# mapleCUx_large_056.net
KiCad netlist of a schematic drawn in EAGLE
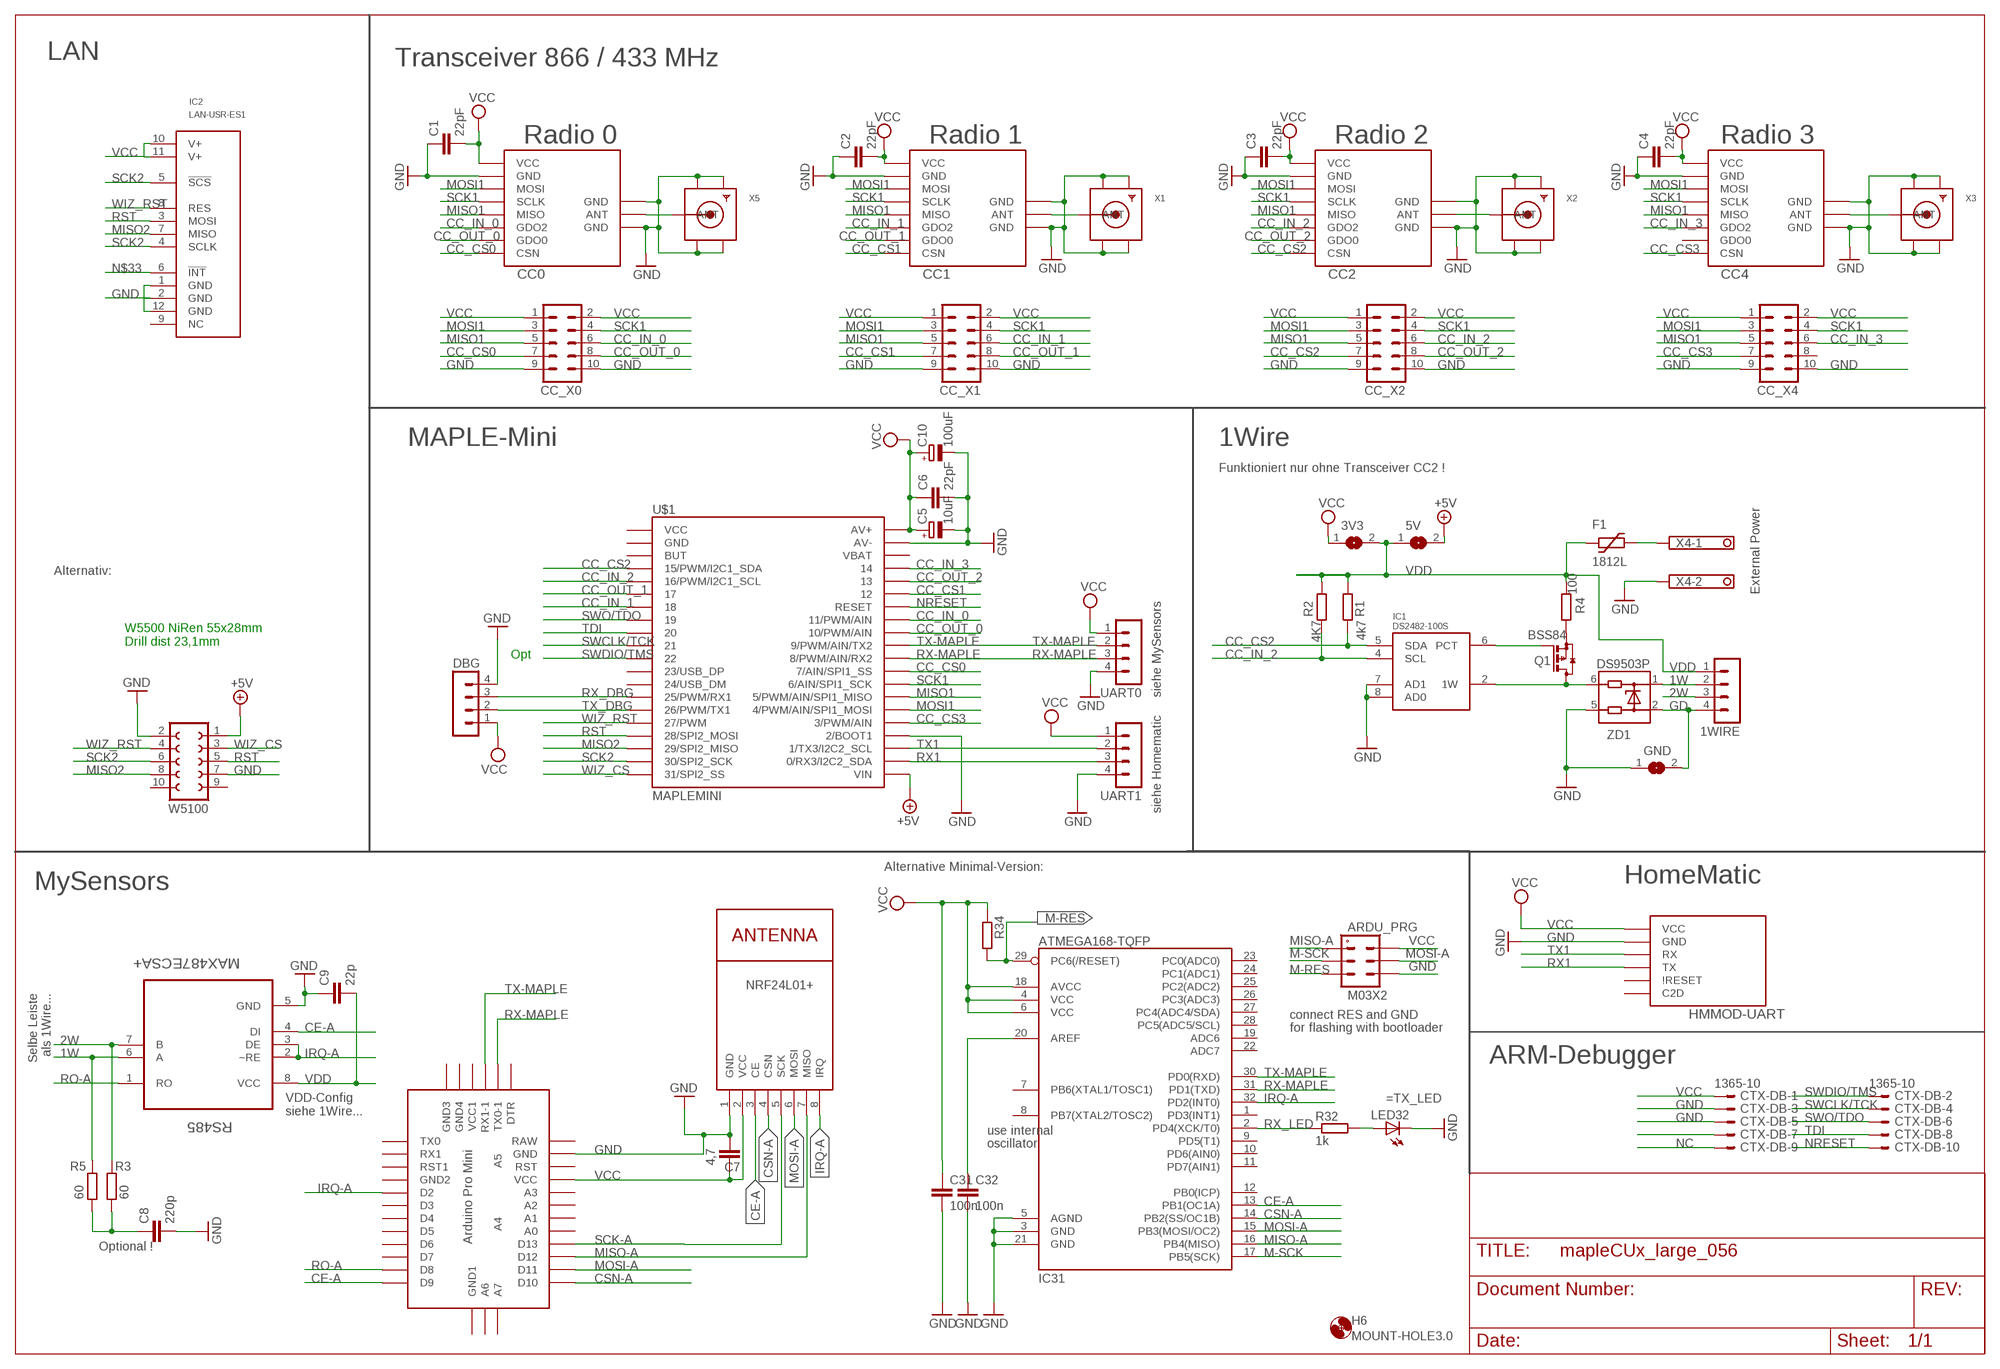
[diagram p0: schematic, sheet 1]

(export (version "E")
  (design (tool "Eeschema 10.0.6"))
  (components
    (comp (ref "1WIRE")
      (value "MA04-1")
      (footprint "eagle-import:MA04-1")
      (libsource (lib "eagle-import") (part "MA04-1"))
    )
    (comp (ref "3V3") (value "SJ") (footprint "eagle-import:SJ") (libsource (lib "eagle-import") (part "SJ")))
    (comp (ref "5V") (value "SJ") (footprint "eagle-import:SJ") (libsource (lib "eagle-import") (part "SJ")))
    (comp (ref "ARDU_PRG")
      (value "M03X2")
      (footprint "eagle-import:2X03-1.27MM_SMD")
      (libsource (lib "eagle-import") (part "M03X2"))
    )
    (comp (ref "C1")
      (value "22pF")
      (footprint "eagle-import:C0805")
      (libsource (lib "eagle-import") (part "C-EUC0805"))
    )
    (comp (ref "C2")
      (value "22pF")
      (footprint "eagle-import:C0805")
      (libsource (lib "eagle-import") (part "C-EUC0805"))
    )
    (comp (ref "C3")
      (value "22pF")
      (footprint "eagle-import:C0805")
      (libsource (lib "eagle-import") (part "C-EUC0805"))
    )
    (comp (ref "C4")
      (value "22pF")
      (footprint "eagle-import:C0805")
      (libsource (lib "eagle-import") (part "C-EUC0805"))
    )
    (comp (ref "C5")
      (value "10uF")
      (footprint "eagle-import:R_2012-12W")
      (libsource (lib "eagle-import") (part "CPOL-EUR/2012-12W"))
    )
    (comp (ref "C6")
      (value "22pF")
      (footprint "eagle-import:C0805")
      (libsource (lib "eagle-import") (part "C-EUC0805"))
    )
    (comp (ref "C7")
      (value "4,7")
      (footprint "eagle-import:C1210")
      (libsource (lib "eagle-import") (part "C-EUC1210"))
    )
    (comp (ref "C8")
      (value "220p")
      (footprint "eagle-import:C0805")
      (libsource (lib "eagle-import") (part "C-EUC0805"))
    )
    (comp (ref "C9")
      (value "22p")
      (footprint "eagle-import:C0805")
      (libsource (lib "eagle-import") (part "C-EUC0805"))
    )
    (comp (ref "C10")
      (value "100uF")
      (footprint "eagle-import:E5-8,5")
      (libsource (lib "eagle-import") (part "CPOL-EUE5-8.5"))
    )
    (comp (ref "C31")
      (value "100n")
      (footprint "eagle-import:C0805")
      (libsource (lib "eagle-import") (part "C-EUC0805"))
    )
    (comp (ref "C32")
      (value "100n")
      (footprint "eagle-import:C0805")
      (libsource (lib "eagle-import") (part "C-EUC0805"))
    )
    (comp (ref "CC0")
      (value "CC1101_MODULE1SMD")
      (footprint "eagle-import:CC1101_MODULE1_SMD")
      (libsource (lib "eagle-import") (part "CC1101_MODULE1SMD"))
    )
    (comp (ref "CC1")
      (value "CC1101_MODULE1SMD")
      (footprint "eagle-import:CC1101_MODULE1_SMD")
      (libsource (lib "eagle-import") (part "CC1101_MODULE1SMD"))
    )
    (comp (ref "CC2")
      (value "CC1101_MODULE1SMD")
      (footprint "eagle-import:CC1101_MODULE1_SMD")
      (libsource (lib "eagle-import") (part "CC1101_MODULE1SMD"))
    )
    (comp (ref "CC4")
      (value "CC1101_MODULE1SMD")
      (footprint "eagle-import:CC1101_MODULE1_SMD")
      (libsource (lib "eagle-import") (part "CC1101_MODULE1SMD"))
    )
    (comp (ref "CC_X0")
      (value "MA05-2")
      (footprint "eagle-import:MA05-2")
      (libsource (lib "eagle-import") (part "MA05-2"))
    )
    (comp (ref "CC_X1")
      (value "MA05-2")
      (footprint "eagle-import:MA05-2")
      (libsource (lib "eagle-import") (part "MA05-2"))
    )
    (comp (ref "CC_X2")
      (value "MA05-2")
      (footprint "eagle-import:MA05-2")
      (libsource (lib "eagle-import") (part "MA05-2"))
    )
    (comp (ref "CC_X4")
      (value "MA05-2")
      (footprint "eagle-import:MA05-2")
      (libsource (lib "eagle-import") (part "MA05-2"))
    )
    (comp (ref "CTX-DB")
      (value "1365-10")
      (footprint "eagle-import:1365-10")
      (libsource (lib "eagle-import") (part "1365-10"))
    )
    (comp (ref "DBG")
      (value "MA04-1")
      (footprint "eagle-import:MA04-1")
      (libsource (lib "eagle-import") (part "MA04-1"))
    )
    (comp (ref "F1")
      (value "1812L")
      (footprint "eagle-import:1812L")
      (libsource (lib "eagle-import") (part "1812L"))
    )
    (comp (ref "GND") (value "SJ") (footprint "eagle-import:SJ") (libsource (lib "eagle-import") (part "SJ")))
    (comp (ref "H6")
      (value "MOUNT-HOLE3.0")
      (footprint "eagle-import:3,0")
      (libsource (lib "eagle-import") (part "MOUNT-HOLE3.0"))
    )
    (comp (ref "HMMOD-UART")
      (value "HM-MOD-UARTDIL")
      (footprint "eagle-import:HM-MOD-UART-DIL")
      (libsource (lib "eagle-import") (part "HM-MOD-UARTDIL"))
    )
    (comp (ref "IC1")
      (value "DS2482-100S")
      (footprint "eagle-import:SO08")
      (libsource (lib "eagle-import") (part "DS2482-100S"))
    )
    (comp (ref "IC2")
      (value "LAN-USR-ES1")
      (footprint "eagle-import:USR-ES1")
      (libsource (lib "eagle-import") (part "LAN-USR-ES1"))
    )
    (comp (ref "IC31")
      (value "ATMEGA168-TQFP")
      (footprint "eagle-import:TQFP32-08")
      (libsource (lib "eagle-import") (part "ATMEGA168-TQFP"))
    )
    (comp (ref "LED32")
      (value "LEDCHIPLED_0805")
      (footprint "eagle-import:CHIPLED_0805")
      (libsource (lib "eagle-import") (part "LEDCHIPLED_0805"))
    )
    (comp (ref "NRF24L01+")
      (value "NRF24L01+")
      (footprint "eagle-import:WIRELESS-NRF24L01")
      (libsource (lib "eagle-import") (part "WIRELESS-NRF24L01"))
    )
    (comp (ref "Q1")
      (value "BSS84")
      (footprint "eagle-import:SOT23")
      (libsource (lib "eagle-import") (part "BSS84"))
    )
    (comp (ref "R1")
      (value "4k7")
      (footprint "eagle-import:R0805")
      (libsource (lib "eagle-import") (part "R-EU_R0805"))
    )
    (comp (ref "R2")
      (value "4K7")
      (footprint "eagle-import:R0805")
      (libsource (lib "eagle-import") (part "R-EU_R0805"))
    )
    (comp (ref "R3")
      (value "60")
      (footprint "eagle-import:R0805")
      (libsource (lib "eagle-import") (part "R-EU_R0805"))
    )
    (comp (ref "R4")
      (value "100")
      (footprint "eagle-import:R0805")
      (libsource (lib "eagle-import") (part "R-EU_R0805"))
    )
    (comp (ref "R5")
      (value "60")
      (footprint "eagle-import:R0805")
      (libsource (lib "eagle-import") (part "R-EU_R0805"))
    )
    (comp (ref "R32")
      (value "1k")
      (footprint "eagle-import:R0805")
      (libsource (lib "eagle-import") (part "R-EU_R0805"))
    )
    (comp (ref "R34")
      (value "R-EU_R0805")
      (footprint "eagle-import:R0805")
      (libsource (lib "eagle-import") (part "R-EU_R0805"))
    )
    (comp (ref "RS485")
      (value "MAX487ECSA+")
      (footprint "eagle-import:SOIC127P600X175-8N")
      (libsource (lib "eagle-import") (part "MAX487ECSA+"))
    )
    (comp (ref "U$1")
      (value "MAPLEMINI")
      (footprint "eagle-import:20-DIP")
      (libsource (lib "eagle-import") (part "MAPLEMINI"))
    )
    (comp (ref "U$2")
      (value "ABK-PRO-MINI")
      (footprint "eagle-import:ABK-PRO-MINI")
      (libsource (lib "eagle-import") (part "ABK-PRO-MINI"))
    )
    (comp (ref "UART0")
      (value "MA04-1")
      (footprint "eagle-import:MA04-1")
      (libsource (lib "eagle-import") (part "MA04-1"))
    )
    (comp (ref "UART1")
      (value "MA04-1")
      (footprint "eagle-import:MA04-1")
      (libsource (lib "eagle-import") (part "MA04-1"))
    )
    (comp (ref "W5100")
      (value "FE05-2")
      (footprint "eagle-import:FE05-2")
      (libsource (lib "eagle-import") (part "FE05-2"))
    )
    (comp (ref "X1")
      (value "SMACONNECTOR_EDGE_UFL")
      (footprint "eagle-import:SMA_EDGELAUNCH_UFL")
      (libsource (lib "eagle-import") (part "SMACONNECTOR_EDGE_UFL"))
    )
    (comp (ref "X2")
      (value "SMACONNECTOR_EDGE_UFL")
      (footprint "eagle-import:SMA_EDGELAUNCH_UFL")
      (libsource (lib "eagle-import") (part "SMACONNECTOR_EDGE_UFL"))
    )
    (comp (ref "X3")
      (value "SMACONNECTOR_EDGE_UFL")
      (footprint "eagle-import:SMA_EDGELAUNCH_UFL")
      (libsource (lib "eagle-import") (part "SMACONNECTOR_EDGE_UFL"))
    )
    (comp (ref "X4")
      (value "1751248")
      (footprint "eagle-import:1751248")
      (libsource (lib "eagle-import") (part "1751248"))
    )
    (comp (ref "X5")
      (value "SMACONNECTOR_EDGE_UFL")
      (footprint "eagle-import:SMA_EDGELAUNCH_UFL")
      (libsource (lib "eagle-import") (part "SMACONNECTOR_EDGE_UFL"))
    )
    (comp (ref "ZD1")
      (value "DS9503P")
      (footprint "eagle-import:TSOC6")
      (libsource (lib "eagle-import") (part "DS9503P"))
    )
  )
  (nets
    (net (code "1") (name "+5V") (class "Default")
      (node (ref "5V") (pin "2") (pinfunction "2_2") (pintype "passive"))
      (node (ref "U$1") (pin "21") (pinfunction "VIN_21") (pintype "bidirectional"))
      (node (ref "W5100") (pin "1") (pinfunction "1_1") (pintype "passive"))
    )
    (net (code "2") (name "/1W") (class "Default")
      (node (ref "1WIRE") (pin "2") (pinfunction "2_2") (pintype "passive"))
      (node (ref "R5") (pin "2") (pinfunction "2_2") (pintype "passive"))
      (node (ref "RS485") (pin "6") (pinfunction "A_6") (pintype "bidirectional"))
      (node (ref "ZD1") (pin "1") (pinfunction "P$1_1") (pintype "passive"))
    )
    (net (code "3") (name "/2W") (class "Default")
      (node (ref "1WIRE") (pin "3") (pinfunction "3_3") (pintype "passive"))
      (node (ref "R3") (pin "2") (pinfunction "2_2") (pintype "passive"))
      (node (ref "RS485") (pin "7") (pinfunction "B_7") (pintype "bidirectional"))
    )
    (net (code "4") (name "/CC_CS0") (class "Default")
      (node (ref "CC0") (pin "CSN") (pinfunction "CSN_CSN") (pintype "bidirectional"))
      (node (ref "CC_X0") (pin "7") (pinfunction "7_7") (pintype "passive"))
      (node (ref "U$1") (pin "29") (pinfunction "7/AIN/SPI1_SS_29") (pintype "bidirectional"))
    )
    (net (code "5") (name "/CC_CS1") (class "Default")
      (node (ref "CC1") (pin "CSN") (pinfunction "CSN_CSN") (pintype "bidirectional"))
      (node (ref "CC_X1") (pin "7") (pinfunction "7_7") (pintype "passive"))
      (node (ref "U$1") (pin "35") (pinfunction "12_35") (pintype "bidirectional"))
    )
    (net (code "6") (name "/CC_CS2") (class "Default")
      (node (ref "CC2") (pin "CSN") (pinfunction "CSN_CSN") (pintype "bidirectional"))
      (node (ref "CC_X2") (pin "7") (pinfunction "7_7") (pintype "passive"))
      (node (ref "IC1") (pin "5") (pinfunction "SDA_5") (pintype "bidirectional"))
      (node (ref "R1") (pin "2") (pinfunction "2_2") (pintype "passive"))
      (node (ref "U$1") (pin "4") (pinfunction "15/PWM/I2C1_SDA_4") (pintype "bidirectional"))
    )
    (net (code "7") (name "/CC_CS3") (class "Default")
      (node (ref "CC4") (pin "CSN") (pinfunction "CSN_CSN") (pintype "bidirectional"))
      (node (ref "CC_X4") (pin "7") (pinfunction "7_7") (pintype "passive"))
      (node (ref "U$1") (pin "25") (pinfunction "3/PWM/AIN_25") (pintype "bidirectional"))
    )
    (net (code "8") (name "/CC_IN_0") (class "Default")
      (node (ref "CC0") (pin "GDO2") (pinfunction "GDO2_GDO2") (pintype "bidirectional"))
      (node (ref "CC_X0") (pin "6") (pinfunction "6_6") (pintype "passive"))
      (node (ref "U$1") (pin "33") (pinfunction "11/PWM/AIN_33") (pintype "bidirectional"))
    )
    (net (code "9") (name "/CC_IN_1") (class "Default")
      (node (ref "CC1") (pin "GDO2") (pinfunction "GDO2_GDO2") (pintype "bidirectional"))
      (node (ref "CC_X1") (pin "6") (pinfunction "6_6") (pintype "passive"))
      (node (ref "U$1") (pin "7") (pinfunction "18_7") (pintype "bidirectional"))
    )
    (net (code "10") (name "/CC_IN_2") (class "Default")
      (node (ref "CC2") (pin "GDO2") (pinfunction "GDO2_GDO2") (pintype "bidirectional"))
      (node (ref "CC_X2") (pin "6") (pinfunction "6_6") (pintype "passive"))
      (node (ref "IC1") (pin "4") (pinfunction "SCL_4") (pintype "input"))
      (node (ref "R2") (pin "2") (pinfunction "2_2") (pintype "passive"))
      (node (ref "U$1") (pin "5") (pinfunction "16/PWM/I2C1_SCL_5") (pintype "bidirectional"))
    )
    (net (code "11") (name "/CC_IN_3") (class "Default")
      (node (ref "CC4") (pin "GDO2") (pinfunction "GDO2_GDO2") (pintype "bidirectional"))
      (node (ref "CC_X4") (pin "6") (pinfunction "6_6") (pintype "passive"))
      (node (ref "U$1") (pin "37") (pinfunction "14_37") (pintype "bidirectional"))
    )
    (net (code "12") (name "/CC_OUT_0") (class "Default")
      (node (ref "CC0") (pin "GDO0") (pinfunction "GDO0_GDO0") (pintype "bidirectional"))
      (node (ref "CC_X0") (pin "8") (pinfunction "8_8") (pintype "passive"))
      (node (ref "U$1") (pin "32") (pinfunction "10/PWM/AIN_32") (pintype "bidirectional"))
    )
    (net (code "13") (name "/CC_OUT_1") (class "Default")
      (node (ref "CC1") (pin "GDO0") (pinfunction "GDO0_GDO0") (pintype "bidirectional"))
      (node (ref "CC_X1") (pin "8") (pinfunction "8_8") (pintype "passive"))
      (node (ref "U$1") (pin "6") (pinfunction "17_6") (pintype "bidirectional"))
    )
    (net (code "14") (name "/CC_OUT_2") (class "Default")
      (node (ref "CC2") (pin "GDO0") (pinfunction "GDO0_GDO0") (pintype "bidirectional"))
      (node (ref "CC_X2") (pin "8") (pinfunction "8_8") (pintype "passive"))
      (node (ref "U$1") (pin "36") (pinfunction "13_36") (pintype "bidirectional"))
    )
    (net (code "15") (name "/GD") (class "Default")
      (node (ref "1WIRE") (pin "4") (pinfunction "4_4") (pintype "passive"))
      (node (ref "GND") (pin "2") (pinfunction "2_2") (pintype "passive"))
      (node (ref "ZD1") (pin "2") (pinfunction "P$2_2") (pintype "passive"))
    )
    (net (code "16") (name "/M-RES") (class "Default")
      (node (ref "ARDU_PRG") (pin "P$5") (pinfunction "5_P$5") (pintype "passive"))
      (node (ref "IC31") (pin "29") (pinfunction "PC6(/RESET)_29") (pintype "bidirectional"))
      (node (ref "R34") (pin "2") (pinfunction "2_2") (pintype "passive"))
    )
    (net (code "17") (name "/M-SCK") (class "Default")
      (node (ref "ARDU_PRG") (pin "P$3") (pinfunction "3_P$3") (pintype "passive"))
      (node (ref "IC31") (pin "17") (pinfunction "PB5(SCK)_17") (pintype "bidirectional"))
    )
    (net (code "18") (name "/MISO-A") (class "Default")
      (node (ref "ARDU_PRG") (pin "P$1") (pinfunction "1_P$1") (pintype "passive"))
      (node (ref "IC31") (pin "16") (pinfunction "PB4(MISO)_16") (pintype "bidirectional"))
      (node (ref "NRF24L01+") (pin "7") (pinfunction "MISO_7") (pintype "bidirectional"))
      (node (ref "U$2") (pin "D12") (pinfunction "D12_D12") (pintype "bidirectional"))
    )
    (net (code "19") (name "/MISO1") (class "Default")
      (node (ref "CC0") (pin "MISO") (pinfunction "MISO_MISO") (pintype "bidirectional"))
      (node (ref "CC1") (pin "MISO") (pinfunction "MISO_MISO") (pintype "bidirectional"))
      (node (ref "CC2") (pin "MISO") (pinfunction "MISO_MISO") (pintype "bidirectional"))
      (node (ref "CC4") (pin "MISO") (pinfunction "MISO_MISO") (pintype "bidirectional"))
      (node (ref "CC_X0") (pin "5") (pinfunction "5_5") (pintype "passive"))
      (node (ref "CC_X1") (pin "5") (pinfunction "5_5") (pintype "passive"))
      (node (ref "CC_X2") (pin "5") (pinfunction "5_5") (pintype "passive"))
      (node (ref "CC_X4") (pin "5") (pinfunction "5_5") (pintype "passive"))
      (node (ref "U$1") (pin "27") (pinfunction "5/PWM/AIN/SPI1_MISO_27") (pintype "bidirectional"))
    )
    (net (code "20") (name "/MISO2") (class "Default")
      (node (ref "IC2") (pin "7") (pinfunction "MISO_7") (pintype "bidirectional"))
      (node (ref "U$1") (pin "18") (pinfunction "29/SPI2_MISO_18") (pintype "bidirectional"))
      (node (ref "W5100") (pin "8") (pinfunction "8_8") (pintype "passive"))
    )
    (net (code "21") (name "/MOSI1") (class "Default")
      (node (ref "CC0") (pin "MOSI") (pinfunction "MOSI_MOSI") (pintype "bidirectional"))
      (node (ref "CC1") (pin "MOSI") (pinfunction "MOSI_MOSI") (pintype "bidirectional"))
      (node (ref "CC2") (pin "MOSI") (pinfunction "MOSI_MOSI") (pintype "bidirectional"))
      (node (ref "CC4") (pin "MOSI") (pinfunction "MOSI_MOSI") (pintype "bidirectional"))
      (node (ref "CC_X0") (pin "3") (pinfunction "3_3") (pintype "passive"))
      (node (ref "CC_X1") (pin "3") (pinfunction "3_3") (pintype "passive"))
      (node (ref "CC_X2") (pin "3") (pinfunction "3_3") (pintype "passive"))
      (node (ref "CC_X4") (pin "3") (pinfunction "3_3") (pintype "passive"))
      (node (ref "U$1") (pin "26") (pinfunction "4/PWM/AIN/SPI1_MOSI_26") (pintype "bidirectional"))
    )
    (net (code "22") (name "/N$33") (class "Default")
      (node (ref "IC2") (pin "6") (pinfunction "~{INT}_6") (pintype "output"))
    )
    (net (code "23") (name "/NC") (class "Default")
      (node (ref "CTX-DB") (pin "9") (pinfunction "S_9") (pintype "passive"))
    )
    (net (code "24") (name "/NRESET") (class "Default")
      (node (ref "CTX-DB") (pin "10") (pinfunction "S_10") (pintype "passive"))
      (node (ref "U$1") (pin "34") (pinfunction "RESET_34") (pintype "bidirectional"))
    )
    (net (code "25") (name "/RO-A") (class "Default")
      (node (ref "RS485") (pin "1") (pinfunction "RO_1") (pintype "output"))
      (node (ref "U$2") (pin "D8") (pinfunction "D8_D8") (pintype "bidirectional"))
    )
    (net (code "26") (name "/RST") (class "Default")
      (node (ref "IC2") (pin "3") (pinfunction "MOSI_3") (pintype "bidirectional"))
      (node (ref "U$1") (pin "17") (pinfunction "28/SPI2_MOSI_17") (pintype "bidirectional"))
      (node (ref "W5100") (pin "5") (pinfunction "5_5") (pintype "passive"))
    )
    (net (code "27") (name "/RX-MAPLE") (class "Default")
      (node (ref "IC31") (pin "31") (pinfunction "PD1(TXD)_31") (pintype "bidirectional"))
      (node (ref "U$1") (pin "30") (pinfunction "8/PWM/AIN/RX2_30") (pintype "bidirectional"))
      (node (ref "U$2") (pin "TX0-1") (pinfunction "TX0-1_TX0-1") (pintype "bidirectional"))
      (node (ref "UART0") (pin "3") (pinfunction "3_3") (pintype "passive"))
    )
    (net (code "28") (name "/RX1") (class "Default")
      (node (ref "HMMOD-UART") (pin "5") (pinfunction "TX_5") (pintype "bidirectional"))
      (node (ref "U$1") (pin "22") (pinfunction "0/RX3/I2C2_SDA_22") (pintype "bidirectional"))
      (node (ref "UART1") (pin "3") (pinfunction "3_3") (pintype "passive"))
    )
    (net (code "29") (name "/RX_DBG") (class "Default")
      (node (ref "DBG") (pin "3") (pinfunction "3_3") (pintype "passive"))
      (node (ref "U$1") (pin "14") (pinfunction "25/PWM/RX1_14") (pintype "bidirectional"))
    )
    (net (code "30") (name "/RX_LED") (class "Default")
      (node (ref "IC31") (pin "2") (pinfunction "PD4(XCK/T0)_2") (pintype "bidirectional"))
      (node (ref "R32") (pin "1") (pinfunction "1_1") (pintype "passive"))
    )
    (net (code "31") (name "/SCK-A") (class "Default")
      (node (ref "NRF24L01+") (pin "5") (pinfunction "SCK_5") (pintype "bidirectional"))
      (node (ref "U$2") (pin "D13") (pinfunction "D13_D13") (pintype "bidirectional"))
    )
    (net (code "32") (name "/SCK1") (class "Default")
      (node (ref "CC0") (pin "SCLK") (pinfunction "SCLK_SCLK") (pintype "bidirectional"))
      (node (ref "CC1") (pin "SCLK") (pinfunction "SCLK_SCLK") (pintype "bidirectional"))
      (node (ref "CC2") (pin "SCLK") (pinfunction "SCLK_SCLK") (pintype "bidirectional"))
      (node (ref "CC4") (pin "SCLK") (pinfunction "SCLK_SCLK") (pintype "bidirectional"))
      (node (ref "CC_X0") (pin "4") (pinfunction "4_4") (pintype "passive"))
      (node (ref "CC_X1") (pin "4") (pinfunction "4_4") (pintype "passive"))
      (node (ref "CC_X2") (pin "4") (pinfunction "4_4") (pintype "passive"))
      (node (ref "CC_X4") (pin "4") (pinfunction "4_4") (pintype "passive"))
      (node (ref "U$1") (pin "28") (pinfunction "6/AIN/SPI1_SCK_28") (pintype "bidirectional"))
    )
    (net (code "33") (name "/SCK2") (class "Default")
      (node (ref "IC2") (pin "4") (pinfunction "SCLK_4") (pintype "input"))
      (node (ref "IC2") (pin "5") (pinfunction "~{SCS}_5") (pintype "input"))
      (node (ref "U$1") (pin "19") (pinfunction "30/SPI2_SCK_19") (pintype "bidirectional"))
      (node (ref "W5100") (pin "6") (pinfunction "6_6") (pintype "passive"))
    )
    (net (code "34") (name "/SWCLK{slash}TCK") (class "Default")
      (node (ref "CTX-DB") (pin "4") (pinfunction "S_4") (pintype "passive"))
      (node (ref "U$1") (pin "10") (pinfunction "21_10") (pintype "bidirectional"))
    )
    (net (code "35") (name "/SWDIO{slash}TMS") (class "Default")
      (node (ref "CTX-DB") (pin "2") (pinfunction "S_2") (pintype "passive"))
      (node (ref "U$1") (pin "11") (pinfunction "22_11") (pintype "bidirectional"))
    )
    (net (code "36") (name "/SWO{slash}TDO") (class "Default")
      (node (ref "CTX-DB") (pin "6") (pinfunction "S_6") (pintype "passive"))
      (node (ref "U$1") (pin "8") (pinfunction "19_8") (pintype "bidirectional"))
    )
    (net (code "37") (name "/TDI") (class "Default")
      (node (ref "CTX-DB") (pin "8") (pinfunction "S_8") (pintype "passive"))
      (node (ref "U$1") (pin "9") (pinfunction "20_9") (pintype "bidirectional"))
    )
    (net (code "38") (name "/TX-MAPLE") (class "Default")
      (node (ref "IC31") (pin "30") (pinfunction "PD0(RXD)_30") (pintype "bidirectional"))
      (node (ref "U$1") (pin "31") (pinfunction "9/PWM/AIN/TX2_31") (pintype "bidirectional"))
      (node (ref "U$2") (pin "RX1-1") (pinfunction "RX1-1_RX1-1") (pintype "bidirectional"))
      (node (ref "UART0") (pin "2") (pinfunction "2_2") (pintype "passive"))
    )
    (net (code "39") (name "/TX1") (class "Default")
      (node (ref "HMMOD-UART") (pin "6") (pinfunction "RX_6") (pintype "bidirectional"))
      (node (ref "U$1") (pin "23") (pinfunction "1/TX3/I2C2_SCL_23") (pintype "bidirectional"))
      (node (ref "UART1") (pin "2") (pinfunction "2_2") (pintype "passive"))
    )
    (net (code "40") (name "/TX_DBG") (class "Default")
      (node (ref "DBG") (pin "2") (pinfunction "2_2") (pintype "passive"))
      (node (ref "U$1") (pin "15") (pinfunction "26/PWM/TX1_15") (pintype "bidirectional"))
    )
    (net (code "41") (name "/VDD") (class "Default")
      (node (ref "1WIRE") (pin "1") (pinfunction "1_1") (pintype "passive"))
      (node (ref "3V3") (pin "2") (pinfunction "2_2") (pintype "passive"))
      (node (ref "5V") (pin "1") (pinfunction "1_1") (pintype "passive"))
      (node (ref "C9") (pin "2") (pinfunction "2_2") (pintype "passive"))
      (node (ref "F1") (pin "P$1") (pinfunction "1_P$1") (pintype "passive"))
      (node (ref "R1") (pin "1") (pinfunction "1_1") (pintype "passive"))
      (node (ref "R2") (pin "1") (pinfunction "1_1") (pintype "passive"))
      (node (ref "R4") (pin "2") (pinfunction "2_2") (pintype "passive"))
      (node (ref "RS485") (pin "8") (pinfunction "VCC_8") (pintype "power_in"))
    )
    (net (code "42") (name "/WIZ_CS") (class "Default")
      (node (ref "U$1") (pin "20") (pinfunction "31/SPI2_SS_20") (pintype "bidirectional"))
      (node (ref "W5100") (pin "3") (pinfunction "3_3") (pintype "passive"))
    )
    (net (code "43") (name "/WIZ_RST") (class "Default")
      (node (ref "IC2") (pin "8") (pinfunction "RES_8") (pintype "input"))
      (node (ref "U$1") (pin "16") (pinfunction "27/PWM_16") (pintype "bidirectional"))
      (node (ref "W5100") (pin "4") (pinfunction "4_4") (pintype "passive"))
    )
    (net (code "44") (name "CE-A") (class "Default")
      (node (ref "IC31") (pin "13") (pinfunction "PB1(OC1A)_13") (pintype "bidirectional"))
      (node (ref "NRF24L01+") (pin "3") (pinfunction "CE_3") (pintype "bidirectional"))
      (node (ref "RS485") (pin "4") (pinfunction "DI_4") (pintype "input"))
      (node (ref "U$2") (pin "D9") (pinfunction "D9_D9") (pintype "bidirectional"))
    )
    (net (code "45") (name "CSN-A") (class "Default")
      (node (ref "IC31") (pin "14") (pinfunction "PB2(SS/OC1B)_14") (pintype "bidirectional"))
      (node (ref "NRF24L01+") (pin "4") (pinfunction "CSN_4") (pintype "bidirectional"))
      (node (ref "U$2") (pin "D10") (pinfunction "D10_D10") (pintype "bidirectional"))
    )
    (net (code "46") (name "GND") (class "Default")
      (node (ref "ARDU_PRG") (pin "P$6") (pinfunction "6_P$6") (pintype "passive"))
      (node (ref "C1") (pin "1") (pinfunction "1_1") (pintype "passive"))
      (node (ref "C10") (pin "-") (pinfunction "-_-") (pintype "passive"))
      (node (ref "C2") (pin "1") (pinfunction "1_1") (pintype "passive"))
      (node (ref "C3") (pin "1") (pinfunction "1_1") (pintype "passive"))
      (node (ref "C31") (pin "2") (pinfunction "2_2") (pintype "passive"))
      (node (ref "C32") (pin "2") (pinfunction "2_2") (pintype "passive"))
      (node (ref "C4") (pin "1") (pinfunction "1_1") (pintype "passive"))
      (node (ref "C5") (pin "-") (pinfunction "-_-") (pintype "passive"))
      (node (ref "C6") (pin "2") (pinfunction "2_2") (pintype "passive"))
      (node (ref "C7") (pin "1") (pinfunction "1_1") (pintype "passive"))
      (node (ref "C8") (pin "2") (pinfunction "2_2") (pintype "passive"))
      (node (ref "C9") (pin "1") (pinfunction "1_1") (pintype "passive"))
      (node (ref "CC0") (pin "GND@0") (pinfunction "GND_GND@0") (pintype "power_in"))
      (node (ref "CC0") (pin "GND@1") (pinfunction "GND_GND@1") (pintype "power_in"))
      (node (ref "CC0") (pin "GND@2") (pinfunction "GND_GND@2") (pintype "power_in"))
      (node (ref "CC1") (pin "GND@0") (pinfunction "GND_GND@0") (pintype "power_in"))
      (node (ref "CC1") (pin "GND@1") (pinfunction "GND_GND@1") (pintype "power_in"))
      (node (ref "CC1") (pin "GND@2") (pinfunction "GND_GND@2") (pintype "power_in"))
      (node (ref "CC2") (pin "GND@0") (pinfunction "GND_GND@0") (pintype "power_in"))
      (node (ref "CC2") (pin "GND@1") (pinfunction "GND_GND@1") (pintype "power_in"))
      (node (ref "CC2") (pin "GND@2") (pinfunction "GND_GND@2") (pintype "power_in"))
      (node (ref "CC4") (pin "GND@0") (pinfunction "GND_GND@0") (pintype "power_in"))
      (node (ref "CC4") (pin "GND@1") (pinfunction "GND_GND@1") (pintype "power_in"))
      (node (ref "CC4") (pin "GND@2") (pinfunction "GND_GND@2") (pintype "power_in"))
      (node (ref "CC_X0") (pin "10") (pinfunction "10_10") (pintype "passive"))
      (node (ref "CC_X0") (pin "9") (pinfunction "9_9") (pintype "passive"))
      (node (ref "CC_X1") (pin "10") (pinfunction "10_10") (pintype "passive"))
      (node (ref "CC_X1") (pin "9") (pinfunction "9_9") (pintype "passive"))
      (node (ref "CC_X2") (pin "10") (pinfunction "10_10") (pintype "passive"))
      (node (ref "CC_X2") (pin "9") (pinfunction "9_9") (pintype "passive"))
      (node (ref "CC_X4") (pin "10") (pinfunction "10_10") (pintype "passive"))
      (node (ref "CC_X4") (pin "9") (pinfunction "9_9") (pintype "passive"))
      (node (ref "CTX-DB") (pin "3") (pinfunction "S_3") (pintype "passive"))
      (node (ref "CTX-DB") (pin "5") (pinfunction "S_5") (pintype "passive"))
      (node (ref "DBG") (pin "4") (pinfunction "4_4") (pintype "passive"))
      (node (ref "GND") (pin "1") (pinfunction "1_1") (pintype "passive"))
      (node (ref "HMMOD-UART") (pin "2") (pinfunction "GND_2") (pintype "power_in"))
      (node (ref "IC1") (pin "7") (pinfunction "AD1_7") (pintype "input"))
      (node (ref "IC1") (pin "8") (pinfunction "AD0_8") (pintype "input"))
      (node (ref "IC2") (pin "1") (pinfunction "GND_1") (pintype "power_in"))
      (node (ref "IC2") (pin "12") (pinfunction "GND_12") (pintype "power_in"))
      (node (ref "IC2") (pin "2") (pinfunction "GND_2") (pintype "power_in"))
      (node (ref "IC31") (pin "21") (pinfunction "GND_21") (pintype "bidirectional"))
      (node (ref "IC31") (pin "3") (pinfunction "GND_3") (pintype "bidirectional"))
      (node (ref "IC31") (pin "5") (pinfunction "AGND_5") (pintype "bidirectional"))
      (node (ref "LED32") (pin "C") (pinfunction "C_C") (pintype "passive"))
      (node (ref "NRF24L01+") (pin "1") (pinfunction "GND_1") (pintype "power_in"))
      (node (ref "RS485") (pin "5") (pinfunction "GND_5") (pintype "passive"))
      (node (ref "U$1") (pin "24") (pinfunction "2/BOOT1_24") (pintype "bidirectional"))
      (node (ref "U$1") (pin "39") (pinfunction "AV-_39") (pintype "bidirectional"))
      (node (ref "U$2") (pin "GND") (pinfunction "GND_GND") (pintype "bidirectional"))
      (node (ref "UART0") (pin "4") (pinfunction "4_4") (pintype "passive"))
      (node (ref "UART1") (pin "4") (pinfunction "4_4") (pintype "passive"))
      (node (ref "W5100") (pin "2") (pinfunction "2_2") (pintype "passive"))
      (node (ref "W5100") (pin "7") (pinfunction "7_7") (pintype "passive"))
      (node (ref "X1") (pin "GND@1") (pinfunction "GND1_GND@1") (pintype "power_in"))
      (node (ref "X1") (pin "GND@2") (pinfunction "GND2_GND@2") (pintype "power_in"))
      (node (ref "X1") (pin "GND@3") (pinfunction "GND3_GND@3") (pintype "power_in"))
      (node (ref "X1") (pin "GND@4") (pinfunction "GND4_GND@4") (pintype "power_in"))
      (node (ref "X2") (pin "GND@1") (pinfunction "GND1_GND@1") (pintype "power_in"))
      (node (ref "X2") (pin "GND@2") (pinfunction "GND2_GND@2") (pintype "power_in"))
      (node (ref "X2") (pin "GND@3") (pinfunction "GND3_GND@3") (pintype "power_in"))
      (node (ref "X2") (pin "GND@4") (pinfunction "GND4_GND@4") (pintype "power_in"))
      (node (ref "X3") (pin "GND@1") (pinfunction "GND1_GND@1") (pintype "power_in"))
      (node (ref "X3") (pin "GND@2") (pinfunction "GND2_GND@2") (pintype "power_in"))
      (node (ref "X3") (pin "GND@3") (pinfunction "GND3_GND@3") (pintype "power_in"))
      (node (ref "X3") (pin "GND@4") (pinfunction "GND4_GND@4") (pintype "power_in"))
      (node (ref "X4") (pin "2") (pinfunction "K_2") (pintype "passive"))
      (node (ref "X5") (pin "GND@1") (pinfunction "GND1_GND@1") (pintype "power_in"))
      (node (ref "X5") (pin "GND@2") (pinfunction "GND2_GND@2") (pintype "power_in"))
      (node (ref "X5") (pin "GND@3") (pinfunction "GND3_GND@3") (pintype "power_in"))
      (node (ref "X5") (pin "GND@4") (pinfunction "GND4_GND@4") (pintype "power_in"))
      (node (ref "ZD1") (pin "5") (pinfunction "P$3_5") (pintype "passive"))
    )
    (net (code "47") (name "IRQ-A") (class "Default")
      (node (ref "IC31") (pin "32") (pinfunction "PD2(INT0)_32") (pintype "bidirectional"))
      (node (ref "NRF24L01+") (pin "8") (pinfunction "IRQ_8") (pintype "bidirectional"))
      (node (ref "RS485") (pin "2") (pinfunction "~{RE}_2") (pintype "input"))
      (node (ref "RS485") (pin "3") (pinfunction "DE_3") (pintype "input"))
      (node (ref "U$2") (pin "D2") (pinfunction "D2_D2") (pintype "bidirectional"))
    )
    (net (code "48") (name "MOSI-A") (class "Default")
      (node (ref "ARDU_PRG") (pin "P$4") (pinfunction "4_P$4") (pintype "passive"))
      (node (ref "IC31") (pin "15") (pinfunction "PB3(MOSI/OC2)_15") (pintype "bidirectional"))
      (node (ref "NRF24L01+") (pin "6") (pinfunction "MOSI_6") (pintype "bidirectional"))
      (node (ref "U$2") (pin "D11") (pinfunction "D11_D11") (pintype "bidirectional"))
    )
    (net (code "49") (name "Net-(C8-Pad1)") (class "Default")
      (node (ref "C8") (pin "1") (pinfunction "1_1") (pintype "passive"))
      (node (ref "R3") (pin "1") (pinfunction "1_1") (pintype "passive"))
      (node (ref "R5") (pin "1") (pinfunction "1_1") (pintype "passive"))
    )
    (net (code "50") (name "Net-(F1-2)") (class "Default")
      (node (ref "F1") (pin "P$2") (pinfunction "2_P$2") (pintype "passive"))
      (node (ref "X4") (pin "1") (pinfunction "K_1") (pintype "passive"))
    )
    (net (code "51") (name "Net-(IC1A-1W)") (class "Default")
      (node (ref "IC1") (pin "2") (pinfunction "1W_2") (pintype "open_collector"))
      (node (ref "Q1") (pin "3") (pinfunction "D_3") (pintype "passive"))
      (node (ref "ZD1") (pin "6") (pinfunction "P$4_6") (pintype "passive"))
    )
    (net (code "52") (name "Net-(IC1A-PCT)") (class "Default")
      (node (ref "IC1") (pin "6") (pinfunction "PCT_6") (pintype "output"))
      (node (ref "Q1") (pin "1") (pinfunction "G_1") (pintype "passive"))
    )
    (net (code "53") (name "Net-(IC31-AREF)") (class "Default")
      (node (ref "C32") (pin "1") (pinfunction "1_1") (pintype "passive"))
      (node (ref "IC31") (pin "20") (pinfunction "AREF_20") (pintype "bidirectional"))
    )
    (net (code "54") (name "Net-(LED32-PadA)") (class "Default")
      (node (ref "LED32") (pin "A") (pinfunction "A_A") (pintype "passive"))
      (node (ref "R32") (pin "2") (pinfunction "2_2") (pintype "passive"))
    )
    (net (code "55") (name "Net-(Q1-S)") (class "Default")
      (node (ref "Q1") (pin "2") (pinfunction "S_2") (pintype "passive"))
      (node (ref "R4") (pin "1") (pinfunction "1_1") (pintype "passive"))
    )
    (net (code "56") (name "Net-(X1-ANT)") (class "Default")
      (node (ref "CC1") (pin "ANT") (pinfunction "ANT_ANT") (pintype "output"))
      (node (ref "X1") (pin "P") (pinfunction "ANT_P") (pintype "bidirectional"))
    )
    (net (code "57") (name "Net-(X2-ANT)") (class "Default")
      (node (ref "CC2") (pin "ANT") (pinfunction "ANT_ANT") (pintype "output"))
      (node (ref "X2") (pin "P") (pinfunction "ANT_P") (pintype "bidirectional"))
    )
    (net (code "58") (name "Net-(X3-ANT)") (class "Default")
      (node (ref "CC4") (pin "ANT") (pinfunction "ANT_ANT") (pintype "output"))
      (node (ref "X3") (pin "P") (pinfunction "ANT_P") (pintype "bidirectional"))
    )
    (net (code "59") (name "Net-(X5-ANT)") (class "Default")
      (node (ref "CC0") (pin "ANT") (pinfunction "ANT_ANT") (pintype "output"))
      (node (ref "X5") (pin "P") (pinfunction "ANT_P") (pintype "bidirectional"))
    )
    (net (code "60") (name "VCC") (class "Default")
      (node (ref "3V3") (pin "1") (pinfunction "1_1") (pintype "passive"))
      (node (ref "ARDU_PRG") (pin "P$2") (pinfunction "2_P$2") (pintype "passive"))
      (node (ref "C1") (pin "2") (pinfunction "2_2") (pintype "passive"))
      (node (ref "C10") (pin "+") (pinfunction "+_+") (pintype "passive"))
      (node (ref "C2") (pin "2") (pinfunction "2_2") (pintype "passive"))
      (node (ref "C3") (pin "2") (pinfunction "2_2") (pintype "passive"))
      (node (ref "C31") (pin "1") (pinfunction "1_1") (pintype "passive"))
      (node (ref "C4") (pin "2") (pinfunction "2_2") (pintype "passive"))
      (node (ref "C5") (pin "+") (pinfunction "+_+") (pintype "passive"))
      (node (ref "C6") (pin "1") (pinfunction "1_1") (pintype "passive"))
      (node (ref "C7") (pin "2") (pinfunction "2_2") (pintype "passive"))
      (node (ref "CC0") (pin "VCC") (pinfunction "VCC_VCC") (pintype "power_in"))
      (node (ref "CC1") (pin "VCC") (pinfunction "VCC_VCC") (pintype "power_in"))
      (node (ref "CC2") (pin "VCC") (pinfunction "VCC_VCC") (pintype "power_in"))
      (node (ref "CC4") (pin "VCC") (pinfunction "VCC_VCC") (pintype "power_in"))
      (node (ref "CC_X0") (pin "1") (pinfunction "1_1") (pintype "passive"))
      (node (ref "CC_X0") (pin "2") (pinfunction "2_2") (pintype "passive"))
      (node (ref "CC_X1") (pin "1") (pinfunction "1_1") (pintype "passive"))
      (node (ref "CC_X1") (pin "2") (pinfunction "2_2") (pintype "passive"))
      (node (ref "CC_X2") (pin "1") (pinfunction "1_1") (pintype "passive"))
      (node (ref "CC_X2") (pin "2") (pinfunction "2_2") (pintype "passive"))
      (node (ref "CC_X4") (pin "1") (pinfunction "1_1") (pintype "passive"))
      (node (ref "CC_X4") (pin "2") (pinfunction "2_2") (pintype "passive"))
      (node (ref "CTX-DB") (pin "1") (pinfunction "S_1") (pintype "passive"))
      (node (ref "DBG") (pin "1") (pinfunction "1_1") (pintype "passive"))
      (node (ref "HMMOD-UART") (pin "1") (pinfunction "VCC_1") (pintype "power_in"))
      (node (ref "IC2") (pin "10") (pinfunction "V+_10") (pintype "power_in"))
      (node (ref "IC2") (pin "11") (pinfunction "V+_11") (pintype "power_in"))
      (node (ref "IC31") (pin "18") (pinfunction "AVCC_18") (pintype "bidirectional"))
      (node (ref "IC31") (pin "4") (pinfunction "VCC_4") (pintype "bidirectional"))
      (node (ref "IC31") (pin "6") (pinfunction "VCC_6") (pintype "bidirectional"))
      (node (ref "NRF24L01+") (pin "2") (pinfunction "VCC_2") (pintype "power_in"))
      (node (ref "R34") (pin "1") (pinfunction "1_1") (pintype "passive"))
      (node (ref "U$1") (pin "40") (pinfunction "AV+_40") (pintype "bidirectional"))
      (node (ref "U$2") (pin "VCC") (pinfunction "VCC_VCC") (pintype "bidirectional"))
      (node (ref "UART0") (pin "1") (pinfunction "1_1") (pintype "passive"))
      (node (ref "UART1") (pin "1") (pinfunction "1_1") (pintype "passive"))
    )
    (net (code "61") (name "unconnected-(CC4-PadGDO0)") (class "Default")
      (node (ref "CC4") (pin "GDO0") (pinfunction "GDO0_GDO0") (pintype "bidirectional"))
    )
    (net (code "62") (name "unconnected-(CC_X4-Pad8)") (class "Default")
      (node (ref "CC_X4") (pin "8") (pinfunction "8_8") (pintype "passive"))
    )
    (net (code "63") (name "unconnected-(CTX-DBH-S-Pad7)") (class "Default")
      (node (ref "CTX-DB") (pin "7") (pinfunction "S_7") (pintype "passive"))
    )
    (net (code "64") (name "unconnected-(HMMOD-UART-C2D-Pad3)") (class "Default")
      (node (ref "HMMOD-UART") (pin "3") (pinfunction "C2D_3") (pintype "bidirectional"))
    )
    (net (code "65") (name "unconnected-(HMMOD-UART-\\~{RESET}-Pad4)") (class "Default")
      (node (ref "HMMOD-UART") (pin "4") (pinfunction "\\~{RESET}_4") (pintype "bidirectional"))
    )
    (net (code "66") (name "unconnected-(IC2-NC-Pad9)") (class "Default")
      (node (ref "IC2") (pin "9") (pinfunction "NC_9") (pintype "no_connect"))
    )
    (net (code "67") (name "unconnected-(IC31-ADC6-Pad19)") (class "Default")
      (node (ref "IC31") (pin "19") (pinfunction "ADC6_19") (pintype "bidirectional"))
    )
    (net (code "68") (name "unconnected-(IC31-ADC7-Pad22)") (class "Default")
      (node (ref "IC31") (pin "22") (pinfunction "ADC7_22") (pintype "bidirectional"))
    )
    (net (code "69") (name "unconnected-(IC31-PB0(ICP)-Pad12)") (class "Default")
      (node (ref "IC31") (pin "12") (pinfunction "PB0(ICP)_12") (pintype "bidirectional"))
    )
    (net (code "70") (name "unconnected-(IC31-PB6(XTAL1{slash}TOSC1)-Pad7)") (class "Default")
      (node (ref "IC31") (pin "7") (pinfunction "PB6(XTAL1/TOSC1)_7") (pintype "bidirectional"))
    )
    (net (code "71") (name "unconnected-(IC31-PB7(XTAL2{slash}TOSC2)-Pad8)") (class "Default")
      (node (ref "IC31") (pin "8") (pinfunction "PB7(XTAL2/TOSC2)_8") (pintype "bidirectional"))
    )
    (net (code "72") (name "unconnected-(IC31-PC0(ADC0)-Pad23)") (class "Default")
      (node (ref "IC31") (pin "23") (pinfunction "PC0(ADC0)_23") (pintype "bidirectional"))
    )
    (net (code "73") (name "unconnected-(IC31-PC1(ADC1)-Pad24)") (class "Default")
      (node (ref "IC31") (pin "24") (pinfunction "PC1(ADC1)_24") (pintype "bidirectional"))
    )
    (net (code "74") (name "unconnected-(IC31-PC2(ADC2)-Pad25)") (class "Default")
      (node (ref "IC31") (pin "25") (pinfunction "PC2(ADC2)_25") (pintype "bidirectional"))
    )
    (net (code "75") (name "unconnected-(IC31-PC3(ADC3)-Pad26)") (class "Default")
      (node (ref "IC31") (pin "26") (pinfunction "PC3(ADC3)_26") (pintype "bidirectional"))
    )
    (net (code "76") (name "unconnected-(IC31-PC4(ADC4{slash}SDA)-Pad27)") (class "Default")
      (node (ref "IC31") (pin "27") (pinfunction "PC4(ADC4/SDA)_27") (pintype "bidirectional"))
    )
    (net (code "77") (name "unconnected-(IC31-PC5(ADC5{slash}SCL)-Pad28)") (class "Default")
      (node (ref "IC31") (pin "28") (pinfunction "PC5(ADC5/SCL)_28") (pintype "bidirectional"))
    )
    (net (code "78") (name "unconnected-(IC31-PD3(INT1)-Pad1)") (class "Default")
      (node (ref "IC31") (pin "1") (pinfunction "PD3(INT1)_1") (pintype "bidirectional"))
    )
    (net (code "79") (name "unconnected-(IC31-PD5(T1)-Pad9)") (class "Default")
      (node (ref "IC31") (pin "9") (pinfunction "PD5(T1)_9") (pintype "bidirectional"))
    )
    (net (code "80") (name "unconnected-(IC31-PD6(AIN0)-Pad10)") (class "Default")
      (node (ref "IC31") (pin "10") (pinfunction "PD6(AIN0)_10") (pintype "bidirectional"))
    )
    (net (code "81") (name "unconnected-(IC31-PD7(AIN1)-Pad11)") (class "Default")
      (node (ref "IC31") (pin "11") (pinfunction "PD7(AIN1)_11") (pintype "bidirectional"))
    )
    (net (code "82") (name "unconnected-(U$1-23{slash}USB_DP-Pad12)") (class "Default")
      (node (ref "U$1") (pin "12") (pinfunction "23/USB_DP_12") (pintype "bidirectional"))
    )
    (net (code "83") (name "unconnected-(U$1-24{slash}USB_DM-Pad13)") (class "Default")
      (node (ref "U$1") (pin "13") (pinfunction "24/USB_DM_13") (pintype "bidirectional"))
    )
    (net (code "84") (name "unconnected-(U$1-BUT-Pad3)") (class "Default")
      (node (ref "U$1") (pin "3") (pinfunction "BUT_3") (pintype "bidirectional"))
    )
    (net (code "85") (name "unconnected-(U$1-GND-Pad2)") (class "Default")
      (node (ref "U$1") (pin "2") (pinfunction "GND_2") (pintype "bidirectional"))
    )
    (net (code "86") (name "unconnected-(U$1-VBAT-Pad38)") (class "Default")
      (node (ref "U$1") (pin "38") (pinfunction "VBAT_38") (pintype "bidirectional"))
    )
    (net (code "87") (name "unconnected-(U$1-VCC-Pad1)") (class "Default")
      (node (ref "U$1") (pin "1") (pinfunction "VCC_1") (pintype "bidirectional"))
    )
    (net (code "88") (name "unconnected-(U$2-GND1-PadGND4)") (class "Default")
      (node (ref "U$2") (pin "GND4") (pinfunction "GND1_GND4") (pintype "bidirectional"))
    )
    (net (code "89") (name "unconnected-(U$2-GND2-PadGND1)") (class "Default")
      (node (ref "U$2") (pin "GND1") (pinfunction "GND2_GND1") (pintype "bidirectional"))
    )
    (net (code "90") (name "unconnected-(U$2-GND3-PadGND2)") (class "Default")
      (node (ref "U$2") (pin "GND2") (pinfunction "GND3_GND2") (pintype "bidirectional"))
    )
    (net (code "91") (name "unconnected-(U$2-GND4-PadGND3)") (class "Default")
      (node (ref "U$2") (pin "GND3") (pinfunction "GND4_GND3") (pintype "bidirectional"))
    )
    (net (code "92") (name "unconnected-(U$2-PadA0)") (class "Default")
      (node (ref "U$2") (pin "A0") (pinfunction "A0_A0") (pintype "bidirectional"))
    )
    (net (code "93") (name "unconnected-(U$2-PadA1)") (class "Default")
      (node (ref "U$2") (pin "A1") (pinfunction "A1_A1") (pintype "bidirectional"))
    )
    (net (code "94") (name "unconnected-(U$2-PadA2)") (class "Default")
      (node (ref "U$2") (pin "A2") (pinfunction "A2_A2") (pintype "bidirectional"))
    )
    (net (code "95") (name "unconnected-(U$2-PadA3)") (class "Default")
      (node (ref "U$2") (pin "A3") (pinfunction "A3_A3") (pintype "bidirectional"))
    )
    (net (code "96") (name "unconnected-(U$2-PadA4)") (class "Default")
      (node (ref "U$2") (pin "A4") (pinfunction "A4_A4") (pintype "bidirectional"))
    )
    (net (code "97") (name "unconnected-(U$2-PadA5)") (class "Default")
      (node (ref "U$2") (pin "A5") (pinfunction "A5_A5") (pintype "bidirectional"))
    )
    (net (code "98") (name "unconnected-(U$2-PadA6)") (class "Default")
      (node (ref "U$2") (pin "A6") (pinfunction "A6_A6") (pintype "bidirectional"))
    )
    (net (code "99") (name "unconnected-(U$2-PadA7)") (class "Default")
      (node (ref "U$2") (pin "A7") (pinfunction "A7_A7") (pintype "bidirectional"))
    )
    (net (code "100") (name "unconnected-(U$2-PadD3)") (class "Default")
      (node (ref "U$2") (pin "D3") (pinfunction "D3_D3") (pintype "bidirectional"))
    )
    (net (code "101") (name "unconnected-(U$2-PadD4)") (class "Default")
      (node (ref "U$2") (pin "D4") (pinfunction "D4_D4") (pintype "bidirectional"))
    )
    (net (code "102") (name "unconnected-(U$2-PadD5)") (class "Default")
      (node (ref "U$2") (pin "D5") (pinfunction "D5_D5") (pintype "bidirectional"))
    )
    (net (code "103") (name "unconnected-(U$2-PadD6)") (class "Default")
      (node (ref "U$2") (pin "D6") (pinfunction "D6_D6") (pintype "bidirectional"))
    )
    (net (code "104") (name "unconnected-(U$2-PadD7)") (class "Default")
      (node (ref "U$2") (pin "D7") (pinfunction "D7_D7") (pintype "bidirectional"))
    )
    (net (code "105") (name "unconnected-(U$2-PadDTR)") (class "Default")
      (node (ref "U$2") (pin "DTR") (pinfunction "DTR_DTR") (pintype "bidirectional"))
    )
    (net (code "106") (name "unconnected-(U$2-PadRAW)") (class "Default")
      (node (ref "U$2") (pin "RAW") (pinfunction "RAW_RAW") (pintype "bidirectional"))
    )
    (net (code "107") (name "unconnected-(U$2-PadRST)") (class "Default")
      (node (ref "U$2") (pin "RST") (pinfunction "RST_RST") (pintype "bidirectional"))
    )
    (net (code "108") (name "unconnected-(U$2-PadRST1)") (class "Default")
      (node (ref "U$2") (pin "RST1") (pinfunction "RST1_RST1") (pintype "bidirectional"))
    )
    (net (code "109") (name "unconnected-(U$2-PadRX1)") (class "Default")
      (node (ref "U$2") (pin "RX1") (pinfunction "RX1_RX1") (pintype "bidirectional"))
    )
    (net (code "110") (name "unconnected-(U$2-PadTX0)") (class "Default")
      (node (ref "U$2") (pin "TX0") (pinfunction "TX0_TX0") (pintype "bidirectional"))
    )
    (net (code "111") (name "unconnected-(U$2-PadVCC1)") (class "Default")
      (node (ref "U$2") (pin "VCC1") (pinfunction "VCC1_VCC1") (pintype "bidirectional"))
    )
    (net (code "112") (name "unconnected-(W5100-Pad9)") (class "Default")
      (node (ref "W5100") (pin "9") (pinfunction "9_9") (pintype "passive"))
    )
    (net (code "113") (name "unconnected-(W5100-Pad10)") (class "Default")
      (node (ref "W5100") (pin "10") (pinfunction "10_10") (pintype "passive"))
    )
  )
)
